# design.net
KiCad netlist of a schematic drawn in EasyEDA Pro
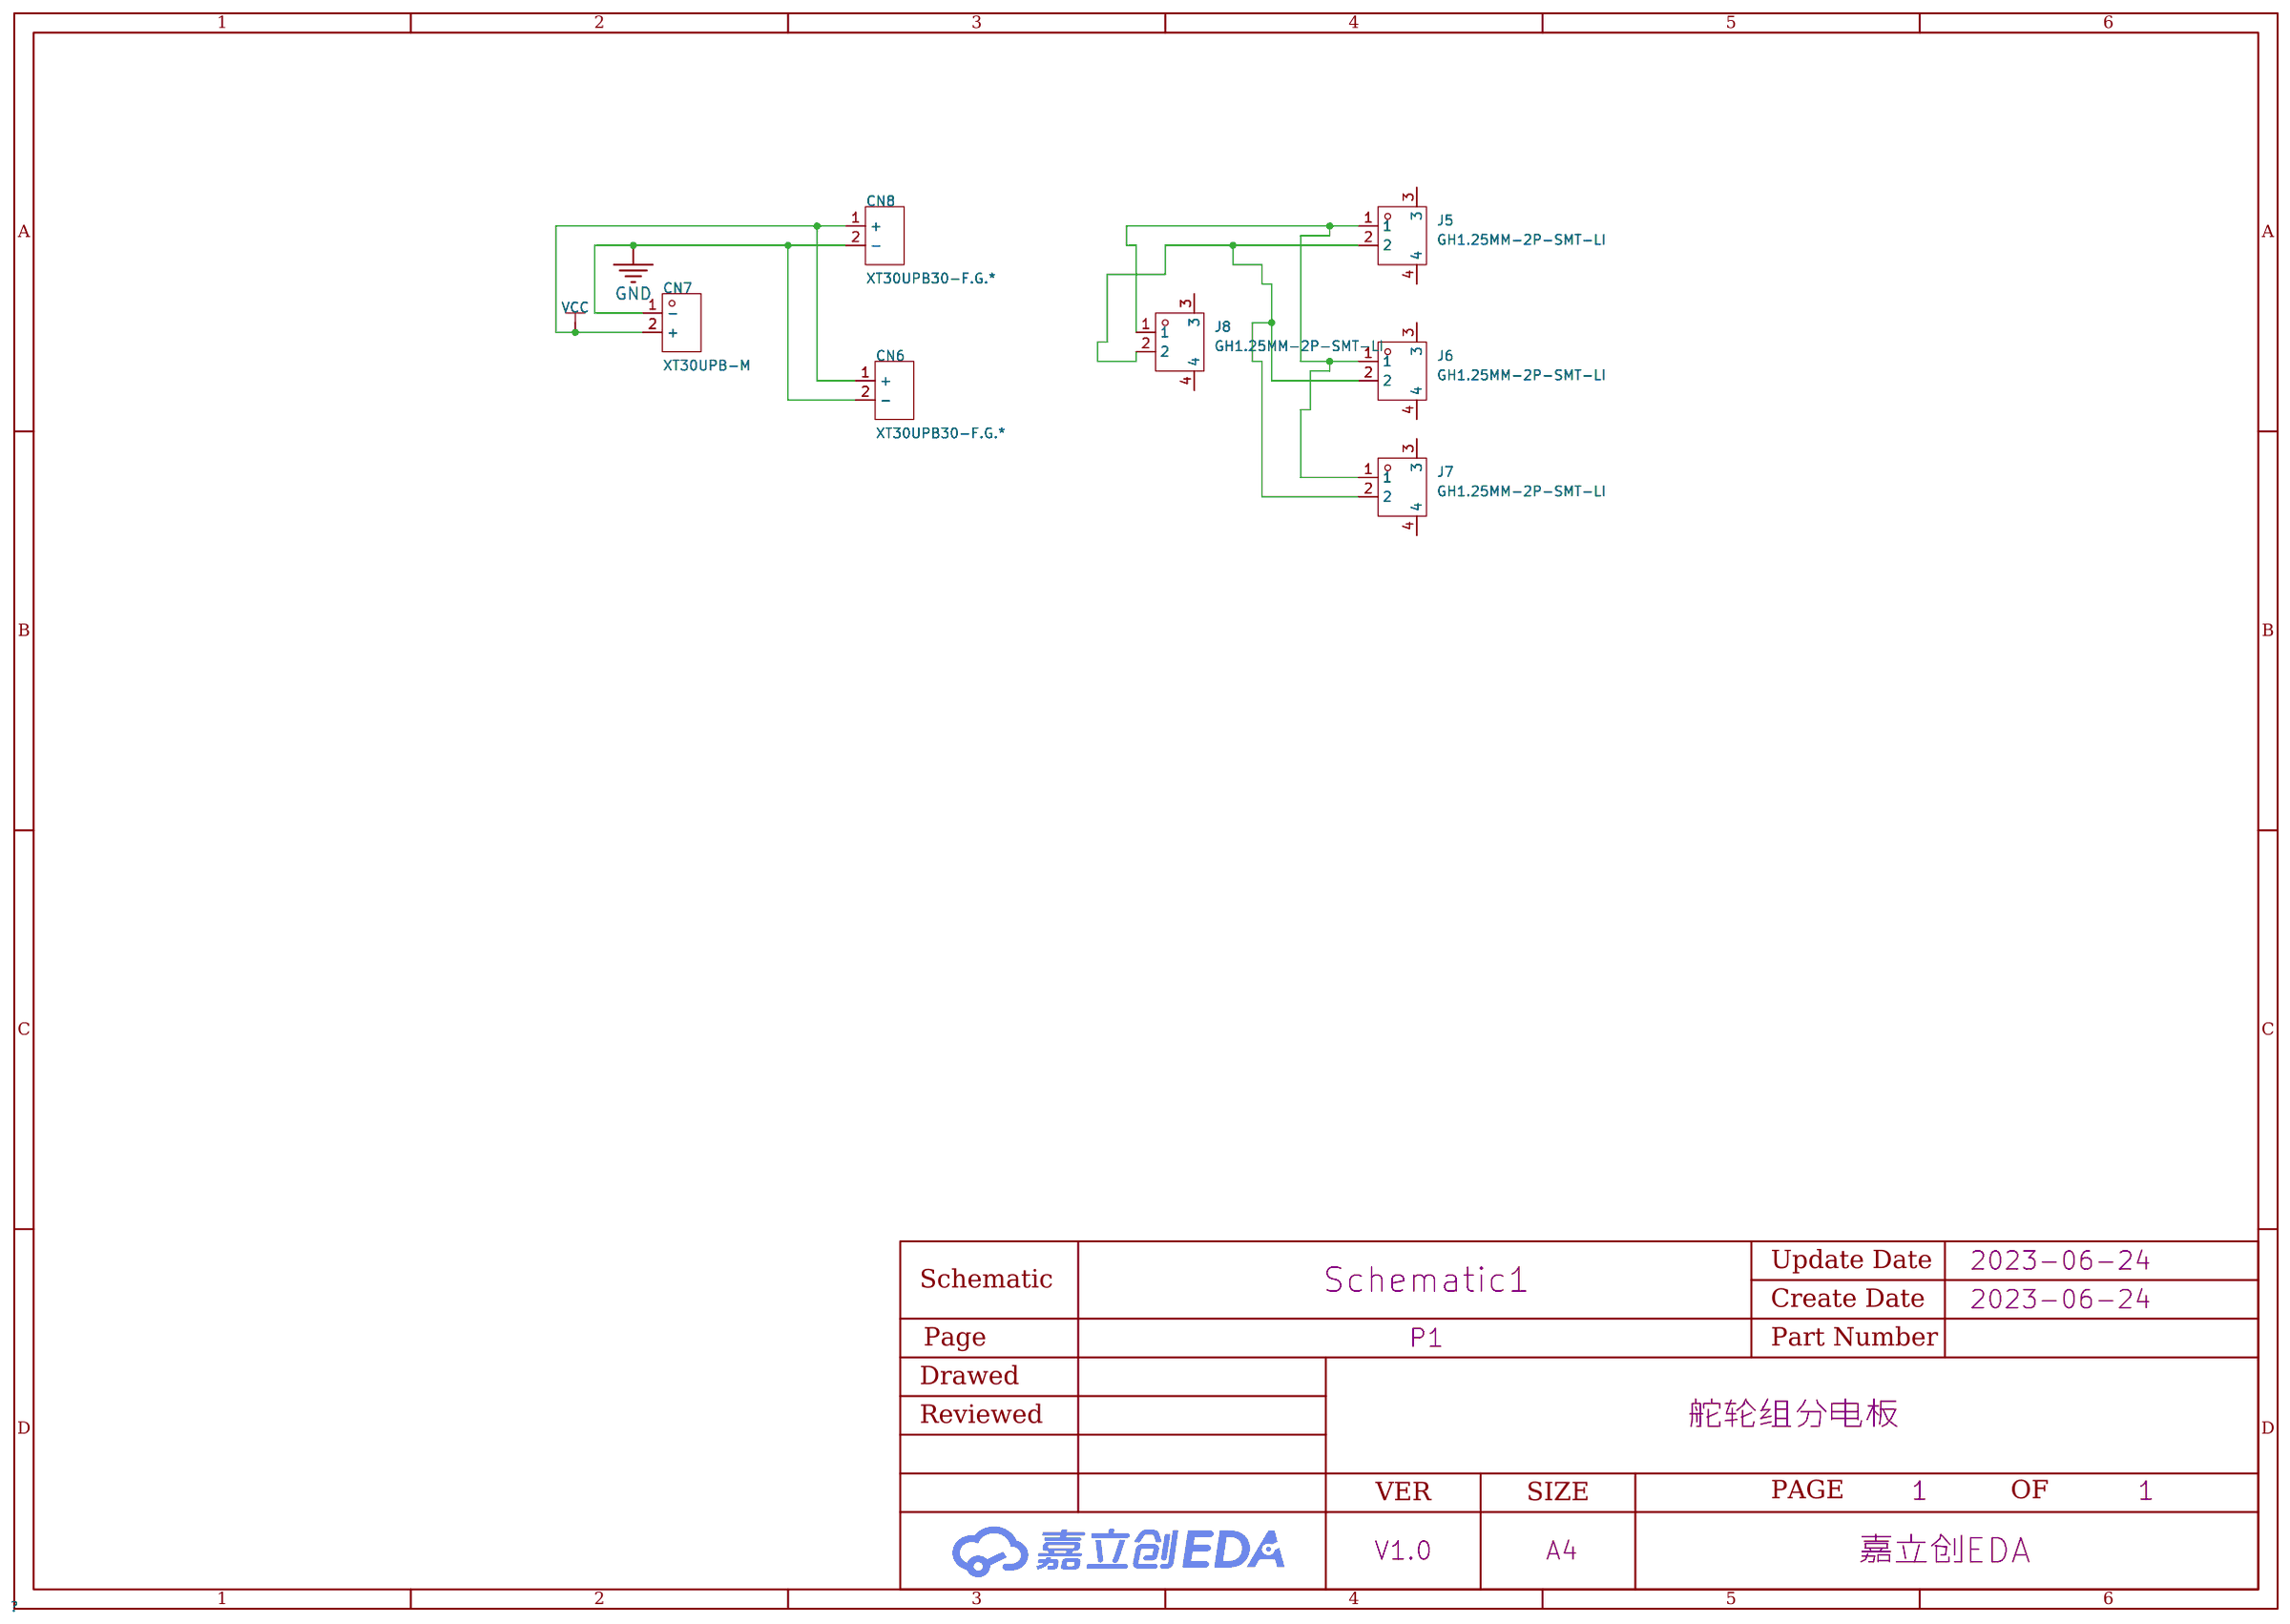
[diagram p0: schematic sheet]

(export (version "E")
  (design (tool "Eeschema 10.0.6"))
  (components
    (comp (ref "CN6")
      (value "XT30UPB30-F.G.*")
      (footprint "easyedapro:CONN-TH_XT30UPB-F")
      (description "模型插头连接器")
      (fields (field (name "Manufacturer") "AMASS(艾迈斯)"))
      (libsource (lib "easyedapro") (part "XT30UPB-F"))
    )
    (comp (ref "CN7")
      (value "XT30UPB-M")
      (footprint "easyedapro:CONN-TH_XT30UPB-M")
      (fields (field (name "Manufacturer") "AMASS(艾迈斯)"))
      (libsource (lib "easyedapro") (part "XT30UPB-M"))
    )
    (comp (ref "CN8")
      (value "XT30UPB30-F.G.*")
      (footprint "easyedapro:CONN-TH_XT30UPB-F")
      (description "模型插头连接器")
      (fields (field (name "Manufacturer") "AMASS(艾迈斯)"))
      (libsource (lib "easyedapro") (part "XT30UPB-F"))
    )
    (comp (ref "J5")
      (value "GH1.25MM-2P-SMT-LI")
      (footprint "easyedapro:CONN-SMD_2P-P1.25_GH1.25-2PLI")
      (libsource (lib "easyedapro") (part "GH1.25MM-2P-SMT-LI"))
    )
    (comp (ref "J6")
      (value "GH1.25MM-2P-SMT-LI")
      (footprint "easyedapro:CONN-SMD_2P-P1.25_GH1.25-2PLI")
      (libsource (lib "easyedapro") (part "GH1.25MM-2P-SMT-LI"))
    )
    (comp (ref "J7")
      (value "GH1.25MM-2P-SMT-LI")
      (footprint "easyedapro:CONN-SMD_2P-P1.25_GH1.25-2PLI")
      (libsource (lib "easyedapro") (part "GH1.25MM-2P-SMT-LI"))
    )
    (comp (ref "J8")
      (value "GH1.25MM-2P-SMT-LI")
      (footprint "easyedapro:CONN-SMD_2P-P1.25_GH1.25-2PLI")
      (libsource (lib "easyedapro") (part "GH1.25MM-2P-SMT-LI"))
    )
  )
  (nets
    (net (code "1") (name "GND") (class "Default")
      (node (ref "CN6") (pin "2") (pinfunction "-_2") (pintype "input"))
      (node (ref "CN7") (pin "1") (pinfunction "-_1") (pintype "input"))
      (node (ref "CN8") (pin "2") (pinfunction "-_2") (pintype "input"))
    )
    (net (code "2") (name "Net-(J5-Pad1)") (class "Default")
      (node (ref "J5") (pin "1") (pinfunction "1_1") (pintype "input"))
      (node (ref "J6") (pin "1") (pinfunction "1_1") (pintype "input"))
      (node (ref "J7") (pin "1") (pinfunction "1_1") (pintype "input"))
      (node (ref "J8") (pin "1") (pinfunction "1_1") (pintype "input"))
    )
    (net (code "3") (name "Net-(J5-Pad2)") (class "Default")
      (node (ref "J5") (pin "2") (pinfunction "2_2") (pintype "input"))
      (node (ref "J6") (pin "2") (pinfunction "2_2") (pintype "input"))
      (node (ref "J7") (pin "2") (pinfunction "2_2") (pintype "input"))
      (node (ref "J8") (pin "2") (pinfunction "2_2") (pintype "input"))
    )
    (net (code "4") (name "VCC") (class "Default")
      (node (ref "CN6") (pin "1") (pinfunction "+_1") (pintype "input"))
      (node (ref "CN7") (pin "2") (pinfunction "+_2") (pintype "input"))
      (node (ref "CN8") (pin "1") (pinfunction "+_1") (pintype "input"))
    )
    (net (code "5") (name "unconnected-(J5-Pad3)") (class "Default")
      (node (ref "J5") (pin "3") (pinfunction "3_3") (pintype "input"))
    )
    (net (code "6") (name "unconnected-(J5-Pad4)") (class "Default")
      (node (ref "J5") (pin "4") (pinfunction "4_4") (pintype "input"))
    )
    (net (code "7") (name "unconnected-(J6-Pad3)") (class "Default")
      (node (ref "J6") (pin "3") (pinfunction "3_3") (pintype "input"))
    )
    (net (code "8") (name "unconnected-(J6-Pad4)") (class "Default")
      (node (ref "J6") (pin "4") (pinfunction "4_4") (pintype "input"))
    )
    (net (code "9") (name "unconnected-(J7-Pad3)") (class "Default")
      (node (ref "J7") (pin "3") (pinfunction "3_3") (pintype "input"))
    )
    (net (code "10") (name "unconnected-(J7-Pad4)") (class "Default")
      (node (ref "J7") (pin "4") (pinfunction "4_4") (pintype "input"))
    )
    (net (code "11") (name "unconnected-(J8-Pad3)") (class "Default")
      (node (ref "J8") (pin "3") (pinfunction "3_3") (pintype "input"))
    )
    (net (code "12") (name "unconnected-(J8-Pad4)") (class "Default")
      (node (ref "J8") (pin "4") (pinfunction "4_4") (pintype "input"))
    )
  )
)
